# AI_ARTIQ_Driver.net
KiCad netlist of a schematic drawn in Altium Designer
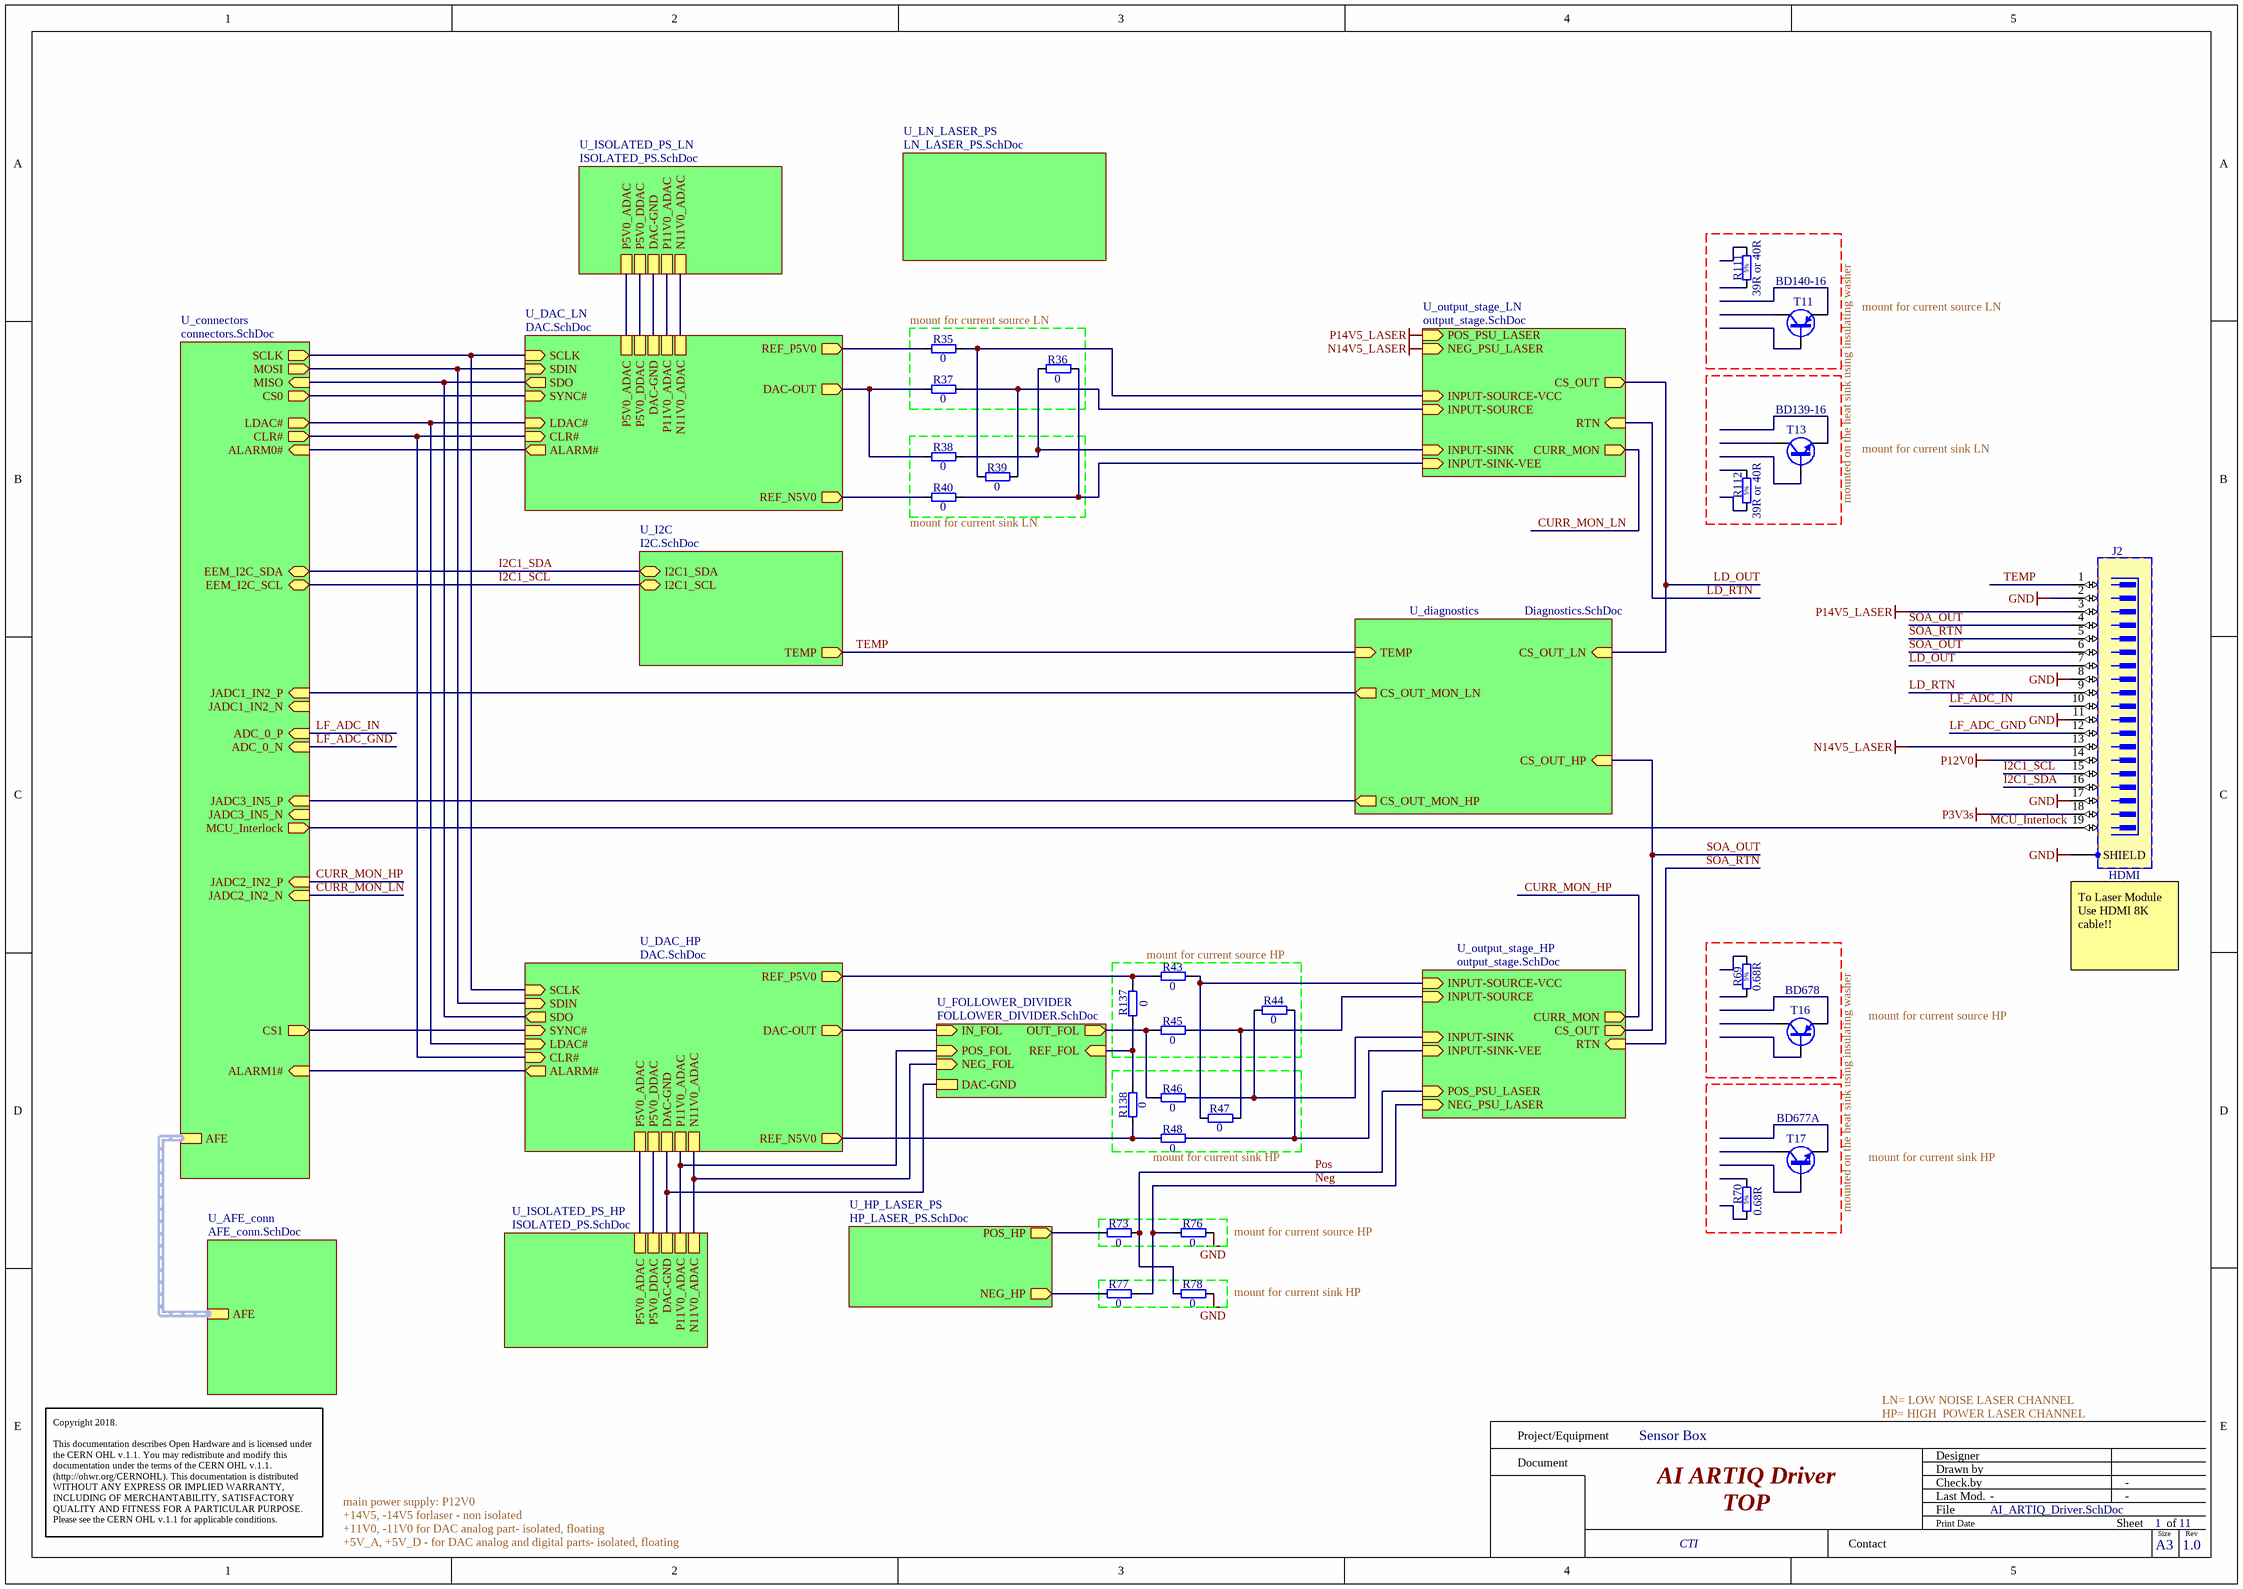
[diagram p0: AI_ARTIQ_Driver.SchDoc]

(export (version "E")
  (design (tool "Eeschema 10.0.6"))
  (components
    (comp (ref "J2")
      (value "HDMI")
      (footprint "MOLEX_47151-0001")
      (description "Connector HDMI 19 Male + 1 Shield")
      (fields
        (field (name "PART NUMBER") "MOLEX_47151-0001")
        (field (name "MANUFACTURER") "MOLEX")
        (field (name "AUTHOR") "CERN DEM JLC")
      )
      (libsource (lib "Connectors") (part "Connector HDMI 19 Male + 1 Shield"))
    )
    (comp (ref "R35")
      (value "0")
      (footprint "RESC2012X60N")
      (description "Resistor")
      (fields
        (field (name "PART NUMBER") "R0805_0R_JUMPER")
        (field (name "MANUFACTURER") "GENERIC")
        (field (name "AUTHOR") "CERN DEM JLC")
      )
      (libsource (lib "Resistors") (part "Resistor"))
    )
    (comp (ref "R36")
      (value "0")
      (footprint "RESC2012X60N")
      (description "Resistor")
      (fields
        (field (name "PART NUMBER") "R0805_0R_JUMPER")
        (field (name "MANUFACTURER") "GENERIC")
        (field (name "AUTHOR") "CERN DEM JLC")
      )
      (libsource (lib "Resistors") (part "Resistor"))
    )
    (comp (ref "R37")
      (value "0")
      (footprint "RESC2012X60N")
      (description "Resistor")
      (fields
        (field (name "PART NUMBER") "R0805_0R_JUMPER")
        (field (name "MANUFACTURER") "GENERIC")
        (field (name "AUTHOR") "CERN DEM JLC")
      )
      (libsource (lib "Resistors") (part "Resistor"))
    )
    (comp (ref "R38")
      (value "0")
      (footprint "RESC2012X60N")
      (description "Resistor")
      (fields
        (field (name "PART NUMBER") "R0805_0R_JUMPER")
        (field (name "MANUFACTURER") "GENERIC")
        (field (name "AUTHOR") "CERN DEM JLC")
      )
      (libsource (lib "Resistors") (part "Resistor"))
    )
    (comp (ref "R39")
      (value "0")
      (footprint "RESC2012X60N")
      (description "Resistor")
      (fields
        (field (name "PART NUMBER") "R0805_0R_JUMPER")
        (field (name "MANUFACTURER") "GENERIC")
        (field (name "AUTHOR") "CERN DEM JLC")
      )
      (libsource (lib "Resistors") (part "Resistor"))
    )
    (comp (ref "R40")
      (value "0")
      (footprint "RESC2012X60N")
      (description "Resistor")
      (fields
        (field (name "PART NUMBER") "R0805_0R_JUMPER")
        (field (name "MANUFACTURER") "GENERIC")
        (field (name "AUTHOR") "CERN DEM JLC")
      )
      (libsource (lib "Resistors") (part "Resistor"))
    )
    (comp (ref "R43")
      (value "0")
      (footprint "RESC2012X60N")
      (description "Resistor")
      (fields
        (field (name "PART NUMBER") "R0805_0R_JUMPER")
        (field (name "MANUFACTURER") "GENERIC")
        (field (name "AUTHOR") "CERN DEM JLC")
      )
      (libsource (lib "Resistors") (part "Resistor"))
    )
    (comp (ref "R44")
      (value "0")
      (footprint "RESC2012X60N")
      (description "Resistor")
      (fields
        (field (name "PART NUMBER") "R0805_0R_JUMPER")
        (field (name "MANUFACTURER") "GENERIC")
        (field (name "AUTHOR") "CERN DEM JLC")
      )
      (libsource (lib "Resistors") (part "Resistor"))
    )
    (comp (ref "R45")
      (value "0")
      (footprint "RESC2012X60N")
      (description "Resistor")
      (fields
        (field (name "PART NUMBER") "R0805_0R_JUMPER")
        (field (name "MANUFACTURER") "GENERIC")
        (field (name "AUTHOR") "CERN DEM JLC")
      )
      (libsource (lib "Resistors") (part "Resistor"))
    )
    (comp (ref "R46")
      (value "0")
      (footprint "RESC2012X60N")
      (description "Resistor")
      (fields
        (field (name "PART NUMBER") "R0805_0R_JUMPER")
        (field (name "MANUFACTURER") "GENERIC")
        (field (name "AUTHOR") "CERN DEM JLC")
      )
      (libsource (lib "Resistors") (part "Resistor"))
    )
    (comp (ref "R47")
      (value "0")
      (footprint "RESC2012X60N")
      (description "Resistor")
      (fields
        (field (name "PART NUMBER") "R0805_0R_JUMPER")
        (field (name "MANUFACTURER") "GENERIC")
        (field (name "AUTHOR") "CERN DEM JLC")
      )
      (libsource (lib "Resistors") (part "Resistor"))
    )
    (comp (ref "R48")
      (value "0")
      (footprint "RESC2012X60N")
      (description "Resistor")
      (fields
        (field (name "PART NUMBER") "R0805_0R_JUMPER")
        (field (name "MANUFACTURER") "GENERIC")
        (field (name "AUTHOR") "CERN DEM JLC")
      )
      (libsource (lib "Resistors") (part "Resistor"))
    )
    (comp (ref "R69")
      (value "0.68R")
      (footprint "RES_VISHAY_RTO50F_v")
      (description "Resistor - 5%")
      (fields
        (field (name "PART NUMBER") "RMF_47R_5%_50W_150PPM_VISHAY_RTO50")
        (field (name "POWER") "50W")
        (field (name "AUTHOR") "CERN DEM JLC")
      )
      (libsource (lib "Resistors") (part "Resistor - 5%"))
    )
    (comp (ref "R70")
      (value "0.68R")
      (footprint "RES_VISHAY_RTO50F_v")
      (description "Resistor - 5%")
      (fields
        (field (name "PART NUMBER") "RMF_47R_5%_50W_150PPM_VISHAY_RTO50")
        (field (name "POWER") "50W")
        (field (name "AUTHOR") "CERN DEM JLC")
      )
      (libsource (lib "Resistors") (part "Resistor - 5%"))
    )
    (comp (ref "R73")
      (value "0")
      (footprint "RESC2012X60N")
      (description "Resistor")
      (fields
        (field (name "PART NUMBER") "R0805_0R_JUMPER")
        (field (name "MANUFACTURER") "GENERIC")
        (field (name "AUTHOR") "CERN DEM JLC")
      )
      (libsource (lib "Resistors") (part "Resistor"))
    )
    (comp (ref "R76")
      (value "0")
      (footprint "RESC2012X60N")
      (description "Resistor")
      (fields
        (field (name "PART NUMBER") "R0805_0R_JUMPER")
        (field (name "MANUFACTURER") "GENERIC")
        (field (name "AUTHOR") "CERN DEM JLC")
      )
      (libsource (lib "Resistors") (part "Resistor"))
    )
    (comp (ref "R77")
      (value "0")
      (footprint "RESC2012X60N")
      (description "Resistor")
      (fields
        (field (name "PART NUMBER") "R0805_0R_JUMPER")
        (field (name "MANUFACTURER") "GENERIC")
        (field (name "AUTHOR") "CERN DEM JLC")
      )
      (libsource (lib "Resistors") (part "Resistor"))
    )
    (comp (ref "R78")
      (value "0")
      (footprint "RESC2012X60N")
      (description "Resistor")
      (fields
        (field (name "PART NUMBER") "R0805_0R_JUMPER")
        (field (name "MANUFACTURER") "GENERIC")
        (field (name "AUTHOR") "CERN DEM JLC")
      )
      (libsource (lib "Resistors") (part "Resistor"))
    )
    (comp (ref "R111")
      (value "39R or 40R")
      (footprint "RES_VISHAY_RTO50F_v")
      (description "Resistor - 5%")
      (fields
        (field (name "PART NUMBER") "RMF_47R_5%_50W_150PPM_VISHAY_RTO50")
        (field (name "POWER") "50W")
        (field (name "AUTHOR") "CERN DEM JLC")
      )
      (libsource (lib "Resistors") (part "Resistor - 5%"))
    )
    (comp (ref "R112")
      (value "39R or 40R")
      (footprint "RES_VISHAY_RTO50F_v")
      (description "Resistor - 5%")
      (fields
        (field (name "PART NUMBER") "RMF_47R_5%_50W_150PPM_VISHAY_RTO50")
        (field (name "POWER") "50W")
        (field (name "AUTHOR") "CERN DEM JLC")
      )
      (libsource (lib "Resistors") (part "Resistor - 5%"))
    )
    (comp (ref "R137")
      (value "0")
      (footprint "RESC2012X60N")
      (description "Resistor")
      (fields
        (field (name "PART NUMBER") "R0805_0R_JUMPER")
        (field (name "MANUFACTURER") "GENERIC")
        (field (name "AUTHOR") "CERN DEM JLC")
      )
      (libsource (lib "Resistors") (part "Resistor"))
    )
    (comp (ref "R138")
      (value "0")
      (footprint "RESC2012X60N")
      (description "Resistor")
      (fields
        (field (name "PART NUMBER") "R0805_0R_JUMPER")
        (field (name "MANUFACTURER") "GENERIC")
        (field (name "AUTHOR") "CERN DEM JLC")
      )
      (libsource (lib "Resistors") (part "Resistor"))
    )
    (comp (ref "T11")
      (value "BD140-16")
      (footprint "TO-126-v")
      (description "PNP Transistor")
      (fields (field (name "MANUFACTURER") "ST MICROELECTRONICS") (field (name "AUTHOR") "CERN DEM JLC"))
      (libsource (lib "ICs And Semiconductors") (part "PNP E1 C2 B3"))
    )
    (comp (ref "T13")
      (value "BD139-16")
      (footprint "TO-126-v")
      (description "NPN Transistor")
      (fields (field (name "MANUFACTURER") "ST MICROELECTRONICS") (field (name "AUTHOR") "CERN DEM JLC"))
      (libsource (lib "ICs And Semiconductors") (part "NPN E1 C2 B3"))
    )
    (comp (ref "T16")
      (value "BD678")
      (footprint "TO-126-v")
      (description "PNP Transistor")
      (fields (field (name "MANUFACTURER") "ST MICROELECTRONICS") (field (name "AUTHOR") "CERN DEM JLC"))
      (libsource (lib "ICs And Semiconductors") (part "PNP E1 C2 B3"))
    )
    (comp (ref "T17")
      (value "BD677A")
      (footprint "TO-126-v")
      (description "NPN Transistor")
      (fields (field (name "MANUFACTURER") "ST MICROELECTRONICS") (field (name "AUTHOR") "CERN DEM JLC"))
      (libsource (lib "ICs And Semiconductors") (part "NPN E1 C2 B3"))
    )
  )
  (nets
    (net (code "14") (name "/DAC-OUT_1") (class "Default")
      (node (ref "R37") (pin "1") (pinfunction "1_1") (pintype "passive"))
      (node (ref "R38") (pin "1") (pinfunction "1_1") (pintype "passive"))
    )
    (net (code "15") (name "/I2C1_SCL") (class "Default")
      (node (ref "J2") (pin "15") (pinfunction "15_15") (pintype "bidirectional"))
    )
    (net (code "16") (name "/I2C1_SDA") (class "Default")
      (node (ref "J2") (pin "16") (pinfunction "16_16") (pintype "bidirectional"))
    )
    (net (code "17") (name "/INPUT-SINK") (class "Default")
      (node (ref "R36") (pin "1") (pinfunction "1_1") (pintype "passive"))
      (node (ref "R38") (pin "2") (pinfunction "2_2") (pintype "passive"))
    )
    (net (code "18") (name "/INPUT-SINK-VEE") (class "Default")
      (node (ref "R36") (pin "2") (pinfunction "2_2") (pintype "passive"))
      (node (ref "R40") (pin "2") (pinfunction "2_2") (pintype "passive"))
    )
    (net (code "19") (name "/INPUT-SINK-VEE_1") (class "Default")
      (node (ref "R44") (pin "2") (pinfunction "2_2") (pintype "passive"))
      (node (ref "R48") (pin "2") (pinfunction "2_2") (pintype "passive"))
    )
    (net (code "20") (name "/INPUT-SINK_1") (class "Default")
      (node (ref "R44") (pin "1") (pinfunction "1_1") (pintype "passive"))
      (node (ref "R46") (pin "2") (pinfunction "2_2") (pintype "passive"))
    )
    (net (code "21") (name "/INPUT-SOURCE") (class "Default")
      (node (ref "R37") (pin "2") (pinfunction "2_2") (pintype "passive"))
      (node (ref "R39") (pin "2") (pinfunction "2_2") (pintype "passive"))
    )
    (net (code "22") (name "/INPUT-SOURCE-VCC") (class "Default")
      (node (ref "R35") (pin "2") (pinfunction "2_2") (pintype "passive"))
      (node (ref "R39") (pin "1") (pinfunction "1_1") (pintype "passive"))
    )
    (net (code "23") (name "/INPUT-SOURCE-VCC_1") (class "Default")
      (node (ref "R43") (pin "2") (pinfunction "2_2") (pintype "passive"))
      (node (ref "R47") (pin "1") (pinfunction "1_1") (pintype "passive"))
    )
    (net (code "24") (name "/INPUT-SOURCE_1") (class "Default")
      (node (ref "R45") (pin "2") (pinfunction "2_2") (pintype "passive"))
      (node (ref "R47") (pin "2") (pinfunction "2_2") (pintype "passive"))
    )
    (net (code "28") (name "/LD_OUT") (class "Default")
      (node (ref "J2") (pin "7") (pinfunction "7_7") (pintype "bidirectional"))
    )
    (net (code "29") (name "/LD_RTN") (class "Default")
      (node (ref "J2") (pin "9") (pinfunction "9_9") (pintype "bidirectional"))
    )
    (net (code "30") (name "/LF_ADC_GND") (class "Default")
      (node (ref "J2") (pin "12") (pinfunction "12_12") (pintype "bidirectional"))
    )
    (net (code "31") (name "/LF_ADC_IN") (class "Default")
      (node (ref "J2") (pin "10") (pinfunction "10_10") (pintype "bidirectional"))
    )
    (net (code "32") (name "/MCU_Interlock") (class "Default")
      (node (ref "J2") (pin "19") (pinfunction "19_19") (pintype "bidirectional"))
    )
    (net (code "36") (name "/NEG_HP") (class "Default")
      (node (ref "R77") (pin "1") (pinfunction "1_1") (pintype "passive"))
    )
    (net (code "37") (name "/Neg") (class "Default")
      (node (ref "R76") (pin "1") (pinfunction "1_1") (pintype "passive"))
      (node (ref "R77") (pin "2") (pinfunction "2_2") (pintype "passive"))
    )
    (net (code "38") (name "/OUT_FOL") (class "Default")
      (node (ref "R45") (pin "1") (pinfunction "1_1") (pintype "passive"))
      (node (ref "R46") (pin "1") (pinfunction "1_1") (pintype "passive"))
    )
    (net (code "45") (name "/POS_HP") (class "Default")
      (node (ref "R73") (pin "1") (pinfunction "1_1") (pintype "passive"))
    )
    (net (code "46") (name "/Pos") (class "Default")
      (node (ref "R73") (pin "2") (pinfunction "2_2") (pintype "passive"))
      (node (ref "R78") (pin "1") (pinfunction "1_1") (pintype "passive"))
    )
    (net (code "47") (name "/REF_FOL") (class "Default")
      (node (ref "R137") (pin "1") (pinfunction "1_1") (pintype "passive"))
      (node (ref "R138") (pin "2") (pinfunction "2_2") (pintype "passive"))
    )
    (net (code "48") (name "/REF_N5V0") (class "Default")
      (node (ref "R40") (pin "1") (pinfunction "1_1") (pintype "passive"))
    )
    (net (code "49") (name "/REF_N5V0_1") (class "Default")
      (node (ref "R138") (pin "1") (pinfunction "1_1") (pintype "passive"))
      (node (ref "R48") (pin "1") (pinfunction "1_1") (pintype "passive"))
    )
    (net (code "50") (name "/REF_P5V0") (class "Default")
      (node (ref "R35") (pin "1") (pinfunction "1_1") (pintype "passive"))
    )
    (net (code "51") (name "/REF_P5V0_1") (class "Default")
      (node (ref "R137") (pin "2") (pinfunction "2_2") (pintype "passive"))
      (node (ref "R43") (pin "1") (pinfunction "1_1") (pintype "passive"))
    )
    (net (code "54") (name "/SOA_OUT") (class "Default")
      (node (ref "J2") (pin "4") (pinfunction "4_4") (pintype "bidirectional"))
      (node (ref "J2") (pin "6") (pinfunction "6_6") (pintype "bidirectional"))
    )
    (net (code "55") (name "/SOA_RTN") (class "Default")
      (node (ref "J2") (pin "5") (pinfunction "5_5") (pintype "bidirectional"))
    )
    (net (code "56") (name "/TEMP") (class "Default")
      (node (ref "J2") (pin "1") (pinfunction "1_1") (pintype "bidirectional"))
    )
    (net (code "57") (name "GND") (class "Default")
      (node (ref "J2") (pin "11") (pinfunction "11_11") (pintype "bidirectional"))
      (node (ref "J2") (pin "17") (pinfunction "17_17") (pintype "bidirectional"))
      (node (ref "J2") (pin "2") (pinfunction "2_2") (pintype "bidirectional"))
      (node (ref "J2") (pin "8") (pinfunction "8_8") (pintype "bidirectional"))
      (node (ref "J2") (pin "SHIELD") (pinfunction "SHIELD_SHIELD") (pintype "power_in"))
      (node (ref "R76") (pin "2") (pinfunction "2_2") (pintype "passive"))
      (node (ref "R78") (pin "2") (pinfunction "2_2") (pintype "passive"))
    )
    (net (code "58") (name "N14V5_LASER") (class "Default")
      (node (ref "J2") (pin "13") (pinfunction "13_13") (pintype "bidirectional"))
    )
    (net (code "59") (name "P3V3s") (class "Default")
      (node (ref "J2") (pin "18") (pinfunction "18_18") (pintype "bidirectional"))
    )
    (net (code "60") (name "P12V0") (class "Default")
      (node (ref "J2") (pin "14") (pinfunction "14_14") (pintype "bidirectional"))
    )
    (net (code "61") (name "P14V5_LASER") (class "Default")
      (node (ref "J2") (pin "3") (pinfunction "3_3") (pintype "bidirectional"))
    )
    (net (code "62") (name "unconnected-(R69-Pad1)") (class "Default")
      (node (ref "R69") (pin "1") (pinfunction "1_1") (pintype "passive"))
    )
    (net (code "63") (name "unconnected-(R69-Pad2)") (class "Default")
      (node (ref "R69") (pin "2") (pinfunction "2_2") (pintype "passive"))
    )
    (net (code "64") (name "unconnected-(R70-Pad1)") (class "Default")
      (node (ref "R70") (pin "1") (pinfunction "1_1") (pintype "passive"))
    )
    (net (code "65") (name "unconnected-(R70-Pad2)") (class "Default")
      (node (ref "R70") (pin "2") (pinfunction "2_2") (pintype "passive"))
    )
    (net (code "66") (name "unconnected-(R111-Pad1)") (class "Default")
      (node (ref "R111") (pin "1") (pinfunction "1_1") (pintype "passive"))
    )
    (net (code "67") (name "unconnected-(R111-Pad2)") (class "Default")
      (node (ref "R111") (pin "2") (pinfunction "2_2") (pintype "passive"))
    )
    (net (code "68") (name "unconnected-(R112-Pad1)") (class "Default")
      (node (ref "R112") (pin "1") (pinfunction "1_1") (pintype "passive"))
    )
    (net (code "69") (name "unconnected-(R112-Pad2)") (class "Default")
      (node (ref "R112") (pin "2") (pinfunction "2_2") (pintype "passive"))
    )
    (net (code "70") (name "unconnected-(T11-B-Pad3)") (class "Default")
      (node (ref "T11") (pin "3") (pinfunction "B_3") (pintype "passive"))
    )
    (net (code "71") (name "unconnected-(T11-C-Pad2)") (class "Default")
      (node (ref "T11") (pin "2") (pinfunction "C_2") (pintype "passive"))
    )
    (net (code "72") (name "unconnected-(T11-E-Pad1)") (class "Default")
      (node (ref "T11") (pin "1") (pinfunction "E_1") (pintype "passive"))
    )
    (net (code "73") (name "unconnected-(T13-B-Pad3)") (class "Default")
      (node (ref "T13") (pin "3") (pinfunction "B_3") (pintype "passive"))
    )
    (net (code "74") (name "unconnected-(T13-C-Pad2)") (class "Default")
      (node (ref "T13") (pin "2") (pinfunction "C_2") (pintype "passive"))
    )
    (net (code "75") (name "unconnected-(T13-E-Pad1)") (class "Default")
      (node (ref "T13") (pin "1") (pinfunction "E_1") (pintype "passive"))
    )
    (net (code "76") (name "unconnected-(T16-B-Pad3)") (class "Default")
      (node (ref "T16") (pin "3") (pinfunction "B_3") (pintype "passive"))
    )
    (net (code "77") (name "unconnected-(T16-C-Pad2)") (class "Default")
      (node (ref "T16") (pin "2") (pinfunction "C_2") (pintype "passive"))
    )
    (net (code "78") (name "unconnected-(T16-E-Pad1)") (class "Default")
      (node (ref "T16") (pin "1") (pinfunction "E_1") (pintype "passive"))
    )
    (net (code "79") (name "unconnected-(T17-B-Pad3)") (class "Default")
      (node (ref "T17") (pin "3") (pinfunction "B_3") (pintype "passive"))
    )
    (net (code "80") (name "unconnected-(T17-C-Pad2)") (class "Default")
      (node (ref "T17") (pin "2") (pinfunction "C_2") (pintype "passive"))
    )
    (net (code "81") (name "unconnected-(T17-E-Pad1)") (class "Default")
      (node (ref "T17") (pin "1") (pinfunction "E_1") (pintype "passive"))
    )
  )
)
